# 555-blinker.net
KiCad netlist of a schematic drawn in EAGLE
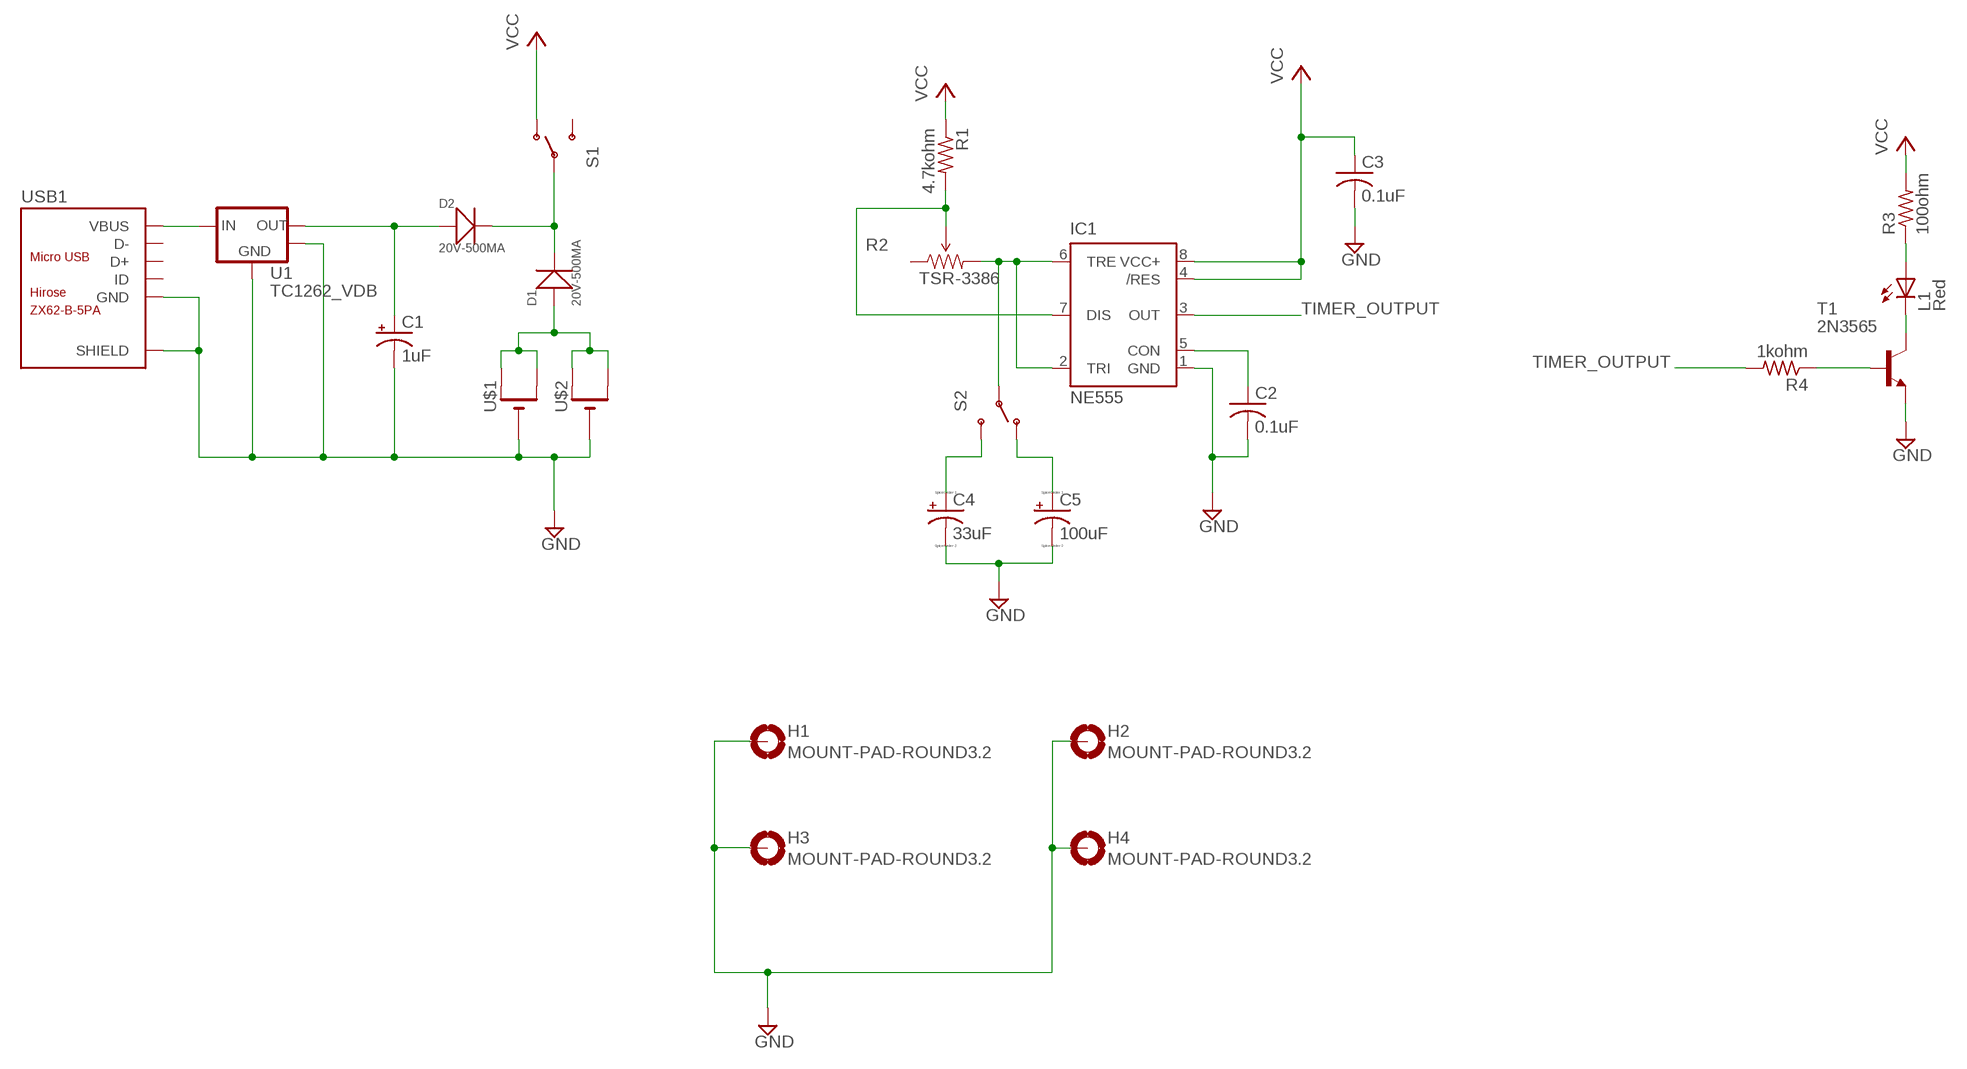
[diagram p0: schematic, sheet 1]

(export (version "E")
  (design (tool "Eeschema 10.0.6"))
  (components
    (comp (ref "C1")
      (value "1uF")
      (footprint "eagle-import:UD-4X5,8_NICHICON")
      (libsource (lib "eagle-import") (part "CPOL-USUD-4X5,8"))
    )
    (comp (ref "C2")
      (value "0.1uF")
      (footprint "eagle-import:C025-025X050")
      (libsource (lib "eagle-import") (part "C-US025-025X050"))
    )
    (comp (ref "C3")
      (value "0.1uF")
      (footprint "eagle-import:C025-025X050")
      (libsource (lib "eagle-import") (part "C-US025-025X050"))
    )
    (comp (ref "C4")
      (value "33uF")
      (footprint "eagle-import:E2-5")
      (libsource (lib "eagle-import") (part "resistor_CPOL-USE2-5"))
    )
    (comp (ref "C5")
      (value "100uF")
      (footprint "eagle-import:E2-5")
      (libsource (lib "eagle-import") (part "resistor_CPOL-USE2-5"))
    )
    (comp (ref "D1")
      (value "20V-500MA")
      (footprint "eagle-import:SOD-123")
      (fields (field (name "MPN") "MBR0520LT1G"))
      (libsource (lib "eagle-import") (part "SMD-DIODE-SCHOTTKY-20V-500MA(SOD-123)"))
    )
    (comp (ref "D2")
      (value "20V-500MA")
      (footprint "eagle-import:SOD-123")
      (fields (field (name "MPN") "MBR0520LT1G"))
      (libsource (lib "eagle-import") (part "SMD-DIODE-SCHOTTKY-20V-500MA(SOD-123)"))
    )
    (comp (ref "H1")
      (value "MOUNT-PAD-ROUND3.2")
      (footprint "eagle-import:3,2-PAD")
      (libsource (lib "eagle-import") (part "MOUNT-PAD-ROUND3.2"))
    )
    (comp (ref "H2")
      (value "MOUNT-PAD-ROUND3.2")
      (footprint "eagle-import:3,2-PAD")
      (libsource (lib "eagle-import") (part "MOUNT-PAD-ROUND3.2"))
    )
    (comp (ref "H3")
      (value "MOUNT-PAD-ROUND3.2")
      (footprint "eagle-import:3,2-PAD")
      (libsource (lib "eagle-import") (part "MOUNT-PAD-ROUND3.2"))
    )
    (comp (ref "H4")
      (value "MOUNT-PAD-ROUND3.2")
      (footprint "eagle-import:3,2-PAD")
      (libsource (lib "eagle-import") (part "MOUNT-PAD-ROUND3.2"))
    )
    (comp (ref "IC1")
      (value "NE555")
      (footprint "eagle-import:DIL-08")
      (fields (field (name "MF") "Arrow Electronics") (field (name "MPN") "NE555N"))
      (libsource (lib "eagle-import") (part "NE555"))
    )
    (comp (ref "L1")
      (value "Red")
      (footprint "eagle-import:LED5MM")
      (libsource (lib "eagle-import") (part "LED5MM"))
    )
    (comp (ref "R1")
      (value "4.7kohm")
      (footprint "eagle-import:0207_10")
      (libsource (lib "eagle-import") (part "R-US_0207/10"))
    )
    (comp (ref "R2")
      (value "TSR-3386")
      (footprint "eagle-import:3386U")
      (libsource (lib "eagle-import") (part "TRIMPOT-PTH-KNOB"))
    )
    (comp (ref "R3")
      (value "100ohm")
      (footprint "eagle-import:0207_10")
      (libsource (lib "eagle-import") (part "R-US_0207/10"))
    )
    (comp (ref "R4")
      (value "1kohm")
      (footprint "eagle-import:0207_10")
      (libsource (lib "eagle-import") (part "R-US_0207/10"))
    )
    (comp (ref "S1")
      (value "SWITCH-SPDTPTH")
      (footprint "eagle-import:SWITCH-SPDT")
      (libsource (lib "eagle-import") (part "SWITCH-SPDTPTH"))
    )
    (comp (ref "S2")
      (value "SWITCH-SPDTPTH")
      (footprint "eagle-import:SWITCH-SPDT")
      (libsource (lib "eagle-import") (part "SWITCH-SPDTPTH"))
    )
    (comp (ref "T1")
      (value "2N3565")
      (footprint "eagle-import:TO92")
      (libsource (lib "eagle-import") (part "2N3565"))
    )
    (comp (ref "U$1")
      (value "CR2032SMT")
      (footprint "eagle-import:CR2032-SMD")
      (libsource (lib "eagle-import") (part "CR2032SMT"))
    )
    (comp (ref "U$2")
      (value "CR2032SMT")
      (footprint "eagle-import:CR2032-SMD")
      (libsource (lib "eagle-import") (part "CR2032SMT"))
    )
    (comp (ref "U1")
      (value "TC1262_VDB")
      (footprint "eagle-import:SOT-223-3")
      (libsource (lib "eagle-import") (part "TC1262_VDB"))
    )
    (comp (ref "USB1")
      (value "ZX62-B-5PA")
      (footprint "eagle-import:MICRO-USB5+6P-SMD-0.65-AB")
      (libsource (lib "eagle-import") (part "MICRO-USB-SMD(ZX62-B-5PA)"))
    )
  )
  (nets
    (net (code "1") (name "/TIMER_OUTPUT") (class "Default")
      (node (ref "IC1") (pin "3") (pinfunction "OUT_3") (pintype "output"))
      (node (ref "R4") (pin "2") (pinfunction "2_2") (pintype "passive"))
    )
    (net (code "2") (name "GND") (class "Default")
      (node (ref "C1") (pin "-") (pinfunction "-_-") (pintype "passive"))
      (node (ref "C2") (pin "2") (pinfunction "2_2") (pintype "passive"))
      (node (ref "C3") (pin "2") (pinfunction "2_2") (pintype "passive"))
      (node (ref "C4") (pin "-") (pinfunction "-_-") (pintype "passive"))
      (node (ref "C5") (pin "-") (pinfunction "-_-") (pintype "passive"))
      (node (ref "H1") (pin "B3,2") (pinfunction "MOUNT_B3,2") (pintype "passive"))
      (node (ref "H2") (pin "B3,2") (pinfunction "MOUNT_B3,2") (pintype "passive"))
      (node (ref "H3") (pin "B3,2") (pinfunction "MOUNT_B3,2") (pintype "passive"))
      (node (ref "H4") (pin "B3,2") (pinfunction "MOUNT_B3,2") (pintype "passive"))
      (node (ref "IC1") (pin "1") (pinfunction "GND_1") (pintype "power_in"))
      (node (ref "T1") (pin "3") (pinfunction "E_3") (pintype "passive"))
      (node (ref "U$1") (pin "-") (pinfunction "-_-") (pintype "passive"))
      (node (ref "U$2") (pin "-") (pinfunction "-_-") (pintype "passive"))
      (node (ref "U1") (pin "2") (pinfunction "GND_2") (pintype "bidirectional"))
      (node (ref "U1") (pin "4") (pinfunction "TAB_4") (pintype "bidirectional"))
      (node (ref "USB1") (pin "5") (pinfunction "GND_5") (pintype "power_in"))
      (node (ref "USB1") (pin "P1") (pinfunction "SHIELD_P1") (pintype "power_in"))
      (node (ref "USB1") (pin "P2") (pinfunction "SHIELD_P2") (pintype "power_in"))
      (node (ref "USB1") (pin "P3") (pinfunction "SHIELD_P3") (pintype "power_in"))
      (node (ref "USB1") (pin "P4") (pinfunction "SHIELD_P4") (pintype "power_in"))
      (node (ref "USB1") (pin "P5") (pinfunction "SHIELD_P5") (pintype "power_in"))
      (node (ref "USB1") (pin "P6") (pinfunction "SHIELD_P6") (pintype "power_in"))
    )
    (net (code "3") (name "Net-(IC1-CON)") (class "Default")
      (node (ref "C2") (pin "1") (pinfunction "1_1") (pintype "passive"))
      (node (ref "IC1") (pin "5") (pinfunction "CON_5") (pintype "input"))
    )
    (net (code "4") (name "Net-(IC1-DIS)") (class "Default")
      (node (ref "IC1") (pin "7") (pinfunction "DIS_7") (pintype "input"))
      (node (ref "R1") (pin "2") (pinfunction "2_2") (pintype "passive"))
      (node (ref "R2") (pin "2") (pinfunction "WIPER_2") (pintype "passive"))
    )
    (net (code "5") (name "Net-(IC1-TRE)") (class "Default")
      (node (ref "IC1") (pin "2") (pinfunction "TRI_2") (pintype "input"))
      (node (ref "IC1") (pin "6") (pinfunction "TRE_6") (pintype "input"))
      (node (ref "R2") (pin "3") (pinfunction "CW_3") (pintype "passive"))
      (node (ref "S2") (pin "2") (pinfunction "P_2") (pintype "passive"))
    )
    (net (code "6") (name "Net-(L1-C)") (class "Default")
      (node (ref "L1") (pin "K") (pinfunction "C_K") (pintype "passive"))
      (node (ref "T1") (pin "1") (pinfunction "C_1") (pintype "passive"))
    )
    (net (code "7") (name "Net-(L1-PadA)") (class "Default")
      (node (ref "L1") (pin "A") (pinfunction "A_A") (pintype "passive"))
      (node (ref "R3") (pin "1") (pinfunction "1_1") (pintype "passive"))
    )
    (net (code "8") (name "Net-(S1-P)") (class "Default")
      (node (ref "D1") (pin "-") (pinfunction "-_-") (pintype "passive"))
      (node (ref "D2") (pin "-") (pinfunction "-_-") (pintype "passive"))
      (node (ref "S1") (pin "2") (pinfunction "P_2") (pintype "passive"))
    )
    (net (code "9") (name "Net-(S2-O)") (class "Default")
      (node (ref "C5") (pin "+") (pinfunction "+_+") (pintype "passive"))
      (node (ref "S2") (pin "1") (pinfunction "O_1") (pintype "passive"))
    )
    (net (code "10") (name "Net-(S2-S)") (class "Default")
      (node (ref "C4") (pin "+") (pinfunction "+_+") (pintype "passive"))
      (node (ref "S2") (pin "3") (pinfunction "S_3") (pintype "passive"))
    )
    (net (code "11") (name "Net-(T1-B)") (class "Default")
      (node (ref "R4") (pin "1") (pinfunction "1_1") (pintype "passive"))
      (node (ref "T1") (pin "2") (pinfunction "B_2") (pintype "passive"))
    )
    (net (code "12") (name "Net-(U$1-+)") (class "Default")
      (node (ref "D1") (pin "+") (pinfunction "+_+") (pintype "passive"))
      (node (ref "U$1") (pin "+$1") (pinfunction "+_+$1") (pintype "passive"))
      (node (ref "U$1") (pin "+$2") (pinfunction "+1_+$2") (pintype "passive"))
      (node (ref "U$2") (pin "+$1") (pinfunction "+_+$1") (pintype "passive"))
      (node (ref "U$2") (pin "+$2") (pinfunction "+1_+$2") (pintype "passive"))
    )
    (net (code "13") (name "Net-(U1-VIN)") (class "Default")
      (node (ref "U1") (pin "1") (pinfunction "VIN_1") (pintype "bidirectional"))
      (node (ref "USB1") (pin "1") (pinfunction "VBUS_1") (pintype "power_in"))
    )
    (net (code "14") (name "Net-(U1-VOUT)") (class "Default")
      (node (ref "C1") (pin "+") (pinfunction "+_+") (pintype "passive"))
      (node (ref "D2") (pin "+") (pinfunction "+_+") (pintype "passive"))
      (node (ref "U1") (pin "3") (pinfunction "VOUT_3") (pintype "bidirectional"))
    )
    (net (code "15") (name "VCC") (class "Default")
      (node (ref "C3") (pin "1") (pinfunction "1_1") (pintype "passive"))
      (node (ref "IC1") (pin "4") (pinfunction "/RES_4") (pintype "input"))
      (node (ref "IC1") (pin "8") (pinfunction "VCC+_8") (pintype "power_in"))
      (node (ref "R1") (pin "1") (pinfunction "1_1") (pintype "passive"))
      (node (ref "R3") (pin "2") (pinfunction "2_2") (pintype "passive"))
      (node (ref "S1") (pin "1") (pinfunction "O_1") (pintype "passive"))
    )
    (net (code "16") (name "unconnected-(R2-CCW-Pad1)") (class "Default")
      (node (ref "R2") (pin "1") (pinfunction "CCW_1") (pintype "passive"))
    )
    (net (code "17") (name "unconnected-(S1-S-Pad3)") (class "Default")
      (node (ref "S1") (pin "3") (pinfunction "S_3") (pintype "passive"))
    )
    (net (code "18") (name "unconnected-(USB1-D+-Pad3)") (class "Default")
      (node (ref "USB1") (pin "3") (pinfunction "D+_3") (pintype "bidirectional"))
    )
    (net (code "19") (name "unconnected-(USB1-D--Pad2)") (class "Default")
      (node (ref "USB1") (pin "2") (pinfunction "D-_2") (pintype "bidirectional"))
    )
    (net (code "20") (name "unconnected-(USB1-ID-Pad4)") (class "Default")
      (node (ref "USB1") (pin "4") (pinfunction "ID_4") (pintype "bidirectional"))
    )
  )
)
